# 16.net
KiCad netlist of a schematic drawn in Altium Designer
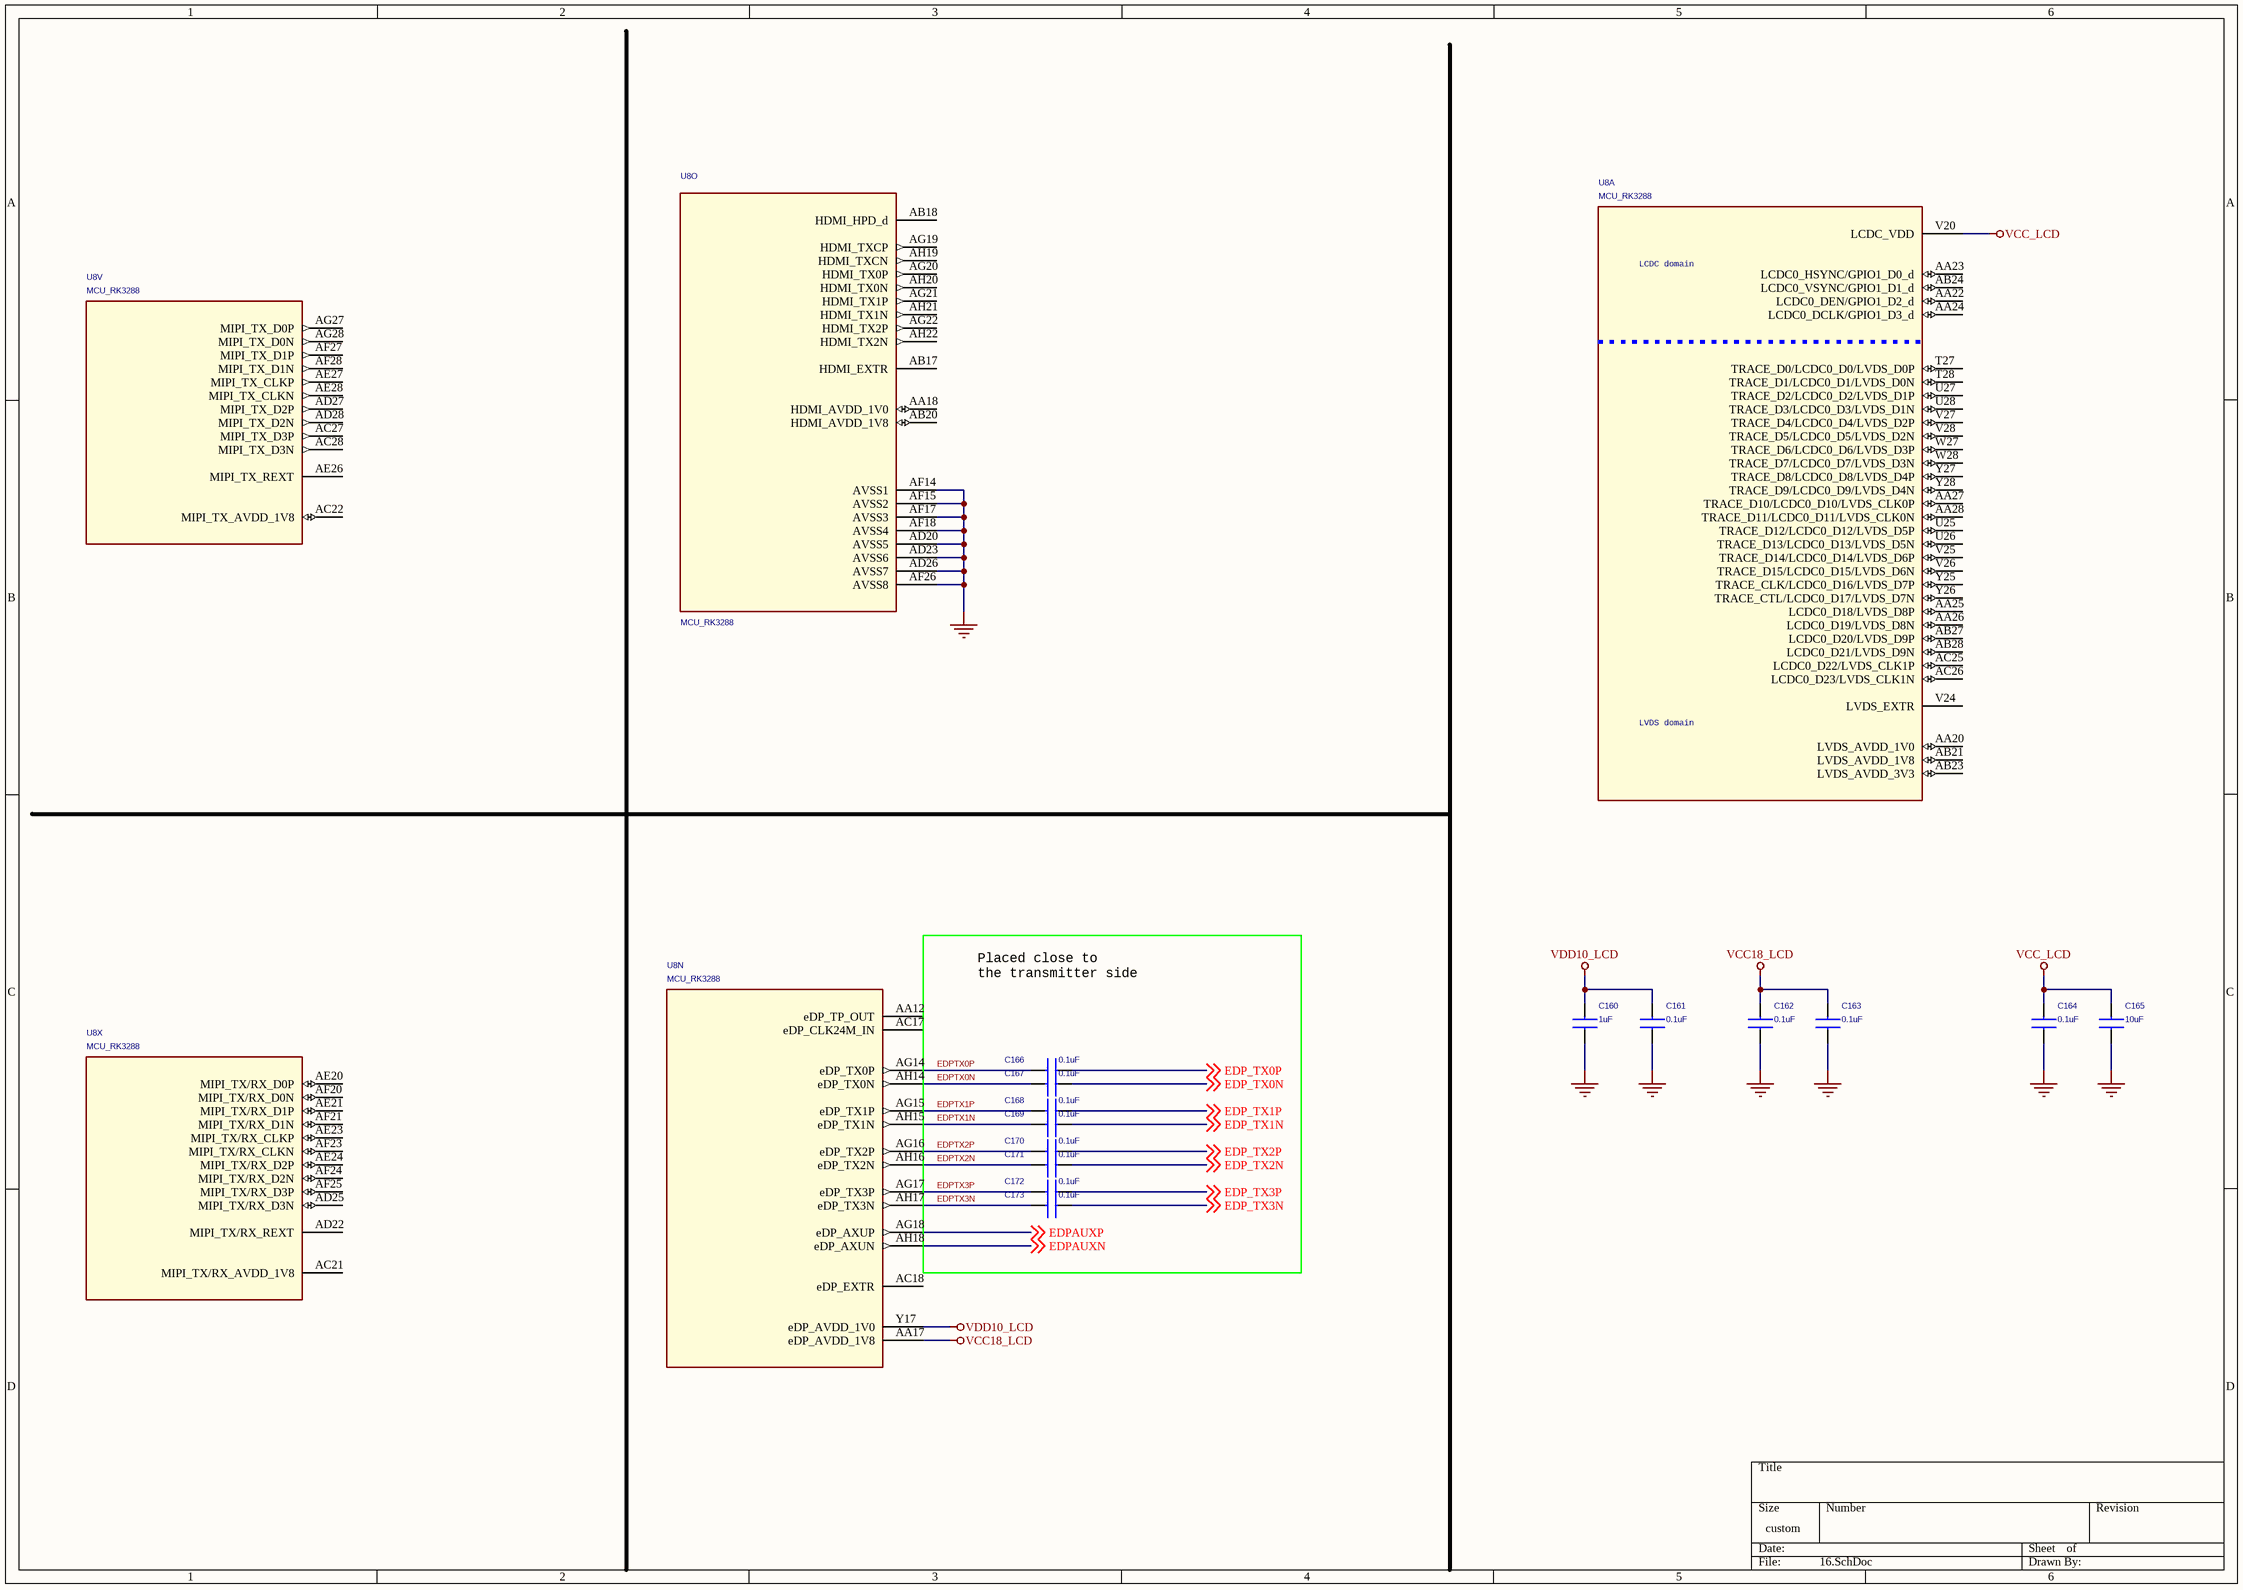
[diagram p0: 16.SchDoc]

(export (version "E")
  (design (tool "Eeschema 10.0.6"))
  (components
    (comp (ref "C160")
      (value "1uF")
      (footprint "C0603")
      (description "CAP,MLCC,100nF,+/-10%,X7R,6.3V,SMD0402")
      (libsource (lib "*") (part "CAP NP_Dup3"))
    )
    (comp (ref "C161")
      (value "0.1uF")
      (footprint "C0603")
      (description "CAP,MLCC,100nF,+/-10%,X7R,6.3V,SMD0402")
      (libsource (lib "*") (part "CAP NP_Dup3"))
    )
    (comp (ref "C162")
      (value "0.1uF")
      (footprint "C0603")
      (description "CAP,MLCC,100nF,+/-10%,X7R,6.3V,SMD0402")
      (libsource (lib "*") (part "CAP NP_Dup3"))
    )
    (comp (ref "C163")
      (value "0.1uF")
      (footprint "C0603")
      (description "CAP,MLCC,100nF,+/-10%,X7R,6.3V,SMD0402")
      (libsource (lib "*") (part "CAP NP_Dup3"))
    )
    (comp (ref "C164")
      (value "0.1uF")
      (footprint "C0603")
      (description "CAP,MLCC,100nF,+/-10%,X7R,6.3V,SMD0402")
      (libsource (lib "*") (part "CAP NP_Dup3"))
    )
    (comp (ref "C165")
      (value "10uF")
      (footprint "C0603")
      (description "CAP,MLCC,4.7uF,+/-10%,X5R,6.3V,SMD0603")
      (libsource (lib "*") (part "CAP NP_Dup3"))
    )
    (comp (ref "C166")
      (value "0.1uF")
      (footprint "C0603")
      (description "CAP,MLCC,100nF,+/-10%,X7R,6.3V,SMD0402")
      (libsource (lib "*") (part "CAP NP_Dup3"))
    )
    (comp (ref "C167")
      (value "0.1uF")
      (footprint "C0603")
      (description "CAP,MLCC,100nF,+/-10%,X7R,6.3V,SMD0402")
      (libsource (lib "*") (part "CAP NP_Dup3"))
    )
    (comp (ref "C168")
      (value "0.1uF")
      (footprint "C0603")
      (description "CAP,MLCC,100nF,+/-10%,X7R,6.3V,SMD0402")
      (libsource (lib "*") (part "CAP NP_Dup3"))
    )
    (comp (ref "C169")
      (value "0.1uF")
      (footprint "C0603")
      (description "CAP,MLCC,100nF,+/-10%,X7R,6.3V,SMD0402")
      (libsource (lib "*") (part "CAP NP_Dup3"))
    )
    (comp (ref "C170")
      (value "0.1uF")
      (footprint "C0603")
      (description "CAP,MLCC,100nF,+/-10%,X7R,6.3V,SMD0402")
      (libsource (lib "*") (part "CAP NP_Dup3"))
    )
    (comp (ref "C171")
      (value "0.1uF")
      (footprint "C0603")
      (description "CAP,MLCC,100nF,+/-10%,X7R,6.3V,SMD0402")
      (libsource (lib "*") (part "CAP NP_Dup3"))
    )
    (comp (ref "C172")
      (value "0.1uF")
      (footprint "C0603")
      (description "CAP,MLCC,100nF,+/-10%,X7R,6.3V,SMD0402")
      (libsource (lib "*") (part "CAP NP_Dup3"))
    )
    (comp (ref "C173")
      (value "0.1uF")
      (footprint "C0603")
      (description "CAP,MLCC,100nF,+/-10%,X7R,6.3V,SMD0402")
      (libsource (lib "*") (part "CAP NP_Dup3"))
    )
    (comp (ref "U8")
      (value "MCU_RK3288")
      (footprint "BGA453-19X19")
      (libsource (lib "*") (part "MCU_RK3288_3"))
    )
  )
  (nets
    (net (code "1") (name "/EDPTX0N") (class "Default")
      (node (ref "C167") (pin "1") (pinfunction "1_1") (pintype "passive"))
      (node (ref "U8") (pin "AH14") (pinfunction "eDP_TX0N_AH14") (pintype "output"))
    )
    (net (code "2") (name "/EDPTX0P") (class "Default")
      (node (ref "C166") (pin "1") (pinfunction "1_1") (pintype "passive"))
      (node (ref "U8") (pin "AG14") (pinfunction "eDP_TX0P_AG14") (pintype "output"))
    )
    (net (code "3") (name "/EDPTX1N") (class "Default")
      (node (ref "C169") (pin "1") (pinfunction "1_1") (pintype "passive"))
      (node (ref "U8") (pin "AH15") (pinfunction "eDP_TX1N_AH15") (pintype "output"))
    )
    (net (code "4") (name "/EDPTX1P") (class "Default")
      (node (ref "C168") (pin "1") (pinfunction "1_1") (pintype "passive"))
      (node (ref "U8") (pin "AG15") (pinfunction "eDP_TX1P_AG15") (pintype "output"))
    )
    (net (code "5") (name "/EDPTX2N") (class "Default")
      (node (ref "C171") (pin "1") (pinfunction "1_1") (pintype "passive"))
      (node (ref "U8") (pin "AH16") (pinfunction "eDP_TX2N_AH16") (pintype "output"))
    )
    (net (code "6") (name "/EDPTX2P") (class "Default")
      (node (ref "C170") (pin "1") (pinfunction "1_1") (pintype "passive"))
      (node (ref "U8") (pin "AG16") (pinfunction "eDP_TX2P_AG16") (pintype "output"))
    )
    (net (code "7") (name "/EDPTX3N") (class "Default")
      (node (ref "C173") (pin "1") (pinfunction "1_1") (pintype "passive"))
      (node (ref "U8") (pin "AH17") (pinfunction "eDP_TX3N_AH17") (pintype "output"))
    )
    (net (code "8") (name "/EDPTX3P") (class "Default")
      (node (ref "C172") (pin "1") (pinfunction "1_1") (pintype "passive"))
      (node (ref "U8") (pin "AG17") (pinfunction "eDP_TX3P_AG17") (pintype "output"))
    )
    (net (code "9") (name "EDPAUXN") (class "Default")
      (node (ref "U8") (pin "AH18") (pinfunction "eDP_AXUN_AH18") (pintype "output"))
    )
    (net (code "10") (name "EDPAUXP") (class "Default")
      (node (ref "U8") (pin "AG18") (pinfunction "eDP_AXUP_AG18") (pintype "output"))
    )
    (net (code "11") (name "EDP_TX0N") (class "Default")
      (node (ref "C167") (pin "2") (pinfunction "2_2") (pintype "passive"))
    )
    (net (code "12") (name "EDP_TX0P") (class "Default")
      (node (ref "C166") (pin "2") (pinfunction "2_2") (pintype "passive"))
    )
    (net (code "13") (name "EDP_TX1N") (class "Default")
      (node (ref "C169") (pin "2") (pinfunction "2_2") (pintype "passive"))
    )
    (net (code "14") (name "EDP_TX1P") (class "Default")
      (node (ref "C168") (pin "2") (pinfunction "2_2") (pintype "passive"))
    )
    (net (code "15") (name "EDP_TX2N") (class "Default")
      (node (ref "C171") (pin "2") (pinfunction "2_2") (pintype "passive"))
    )
    (net (code "16") (name "EDP_TX2P") (class "Default")
      (node (ref "C170") (pin "2") (pinfunction "2_2") (pintype "passive"))
    )
    (net (code "17") (name "EDP_TX3N") (class "Default")
      (node (ref "C173") (pin "2") (pinfunction "2_2") (pintype "passive"))
    )
    (net (code "18") (name "EDP_TX3P") (class "Default")
      (node (ref "C172") (pin "2") (pinfunction "2_2") (pintype "passive"))
    )
    (net (code "19") (name "GND") (class "Default")
      (node (ref "C160") (pin "2") (pinfunction "2_2") (pintype "passive"))
      (node (ref "C161") (pin "2") (pinfunction "2_2") (pintype "passive"))
      (node (ref "C162") (pin "2") (pinfunction "2_2") (pintype "passive"))
      (node (ref "C163") (pin "2") (pinfunction "2_2") (pintype "passive"))
      (node (ref "C164") (pin "2") (pinfunction "2_2") (pintype "passive"))
      (node (ref "C165") (pin "2") (pinfunction "2_2") (pintype "passive"))
      (node (ref "U8") (pin "AD20") (pinfunction "AVSS5_AD20") (pintype "power_in"))
      (node (ref "U8") (pin "AD23") (pinfunction "AVSS6_AD23") (pintype "power_in"))
      (node (ref "U8") (pin "AD26") (pinfunction "AVSS7_AD26") (pintype "power_in"))
      (node (ref "U8") (pin "AF14") (pinfunction "AVSS1_AF14") (pintype "power_in"))
      (node (ref "U8") (pin "AF15") (pinfunction "AVSS2_AF15") (pintype "power_in"))
      (node (ref "U8") (pin "AF17") (pinfunction "AVSS3_AF17") (pintype "power_in"))
      (node (ref "U8") (pin "AF18") (pinfunction "AVSS4_AF18") (pintype "power_in"))
      (node (ref "U8") (pin "AF26") (pinfunction "AVSS8_AF26") (pintype "power_in"))
    )
    (net (code "20") (name "VCC18_LCD") (class "Default")
      (node (ref "C162") (pin "1") (pinfunction "1_1") (pintype "passive"))
      (node (ref "C163") (pin "1") (pinfunction "1_1") (pintype "passive"))
      (node (ref "U8") (pin "AA17") (pinfunction "eDP_AVDD_1V8_AA17") (pintype "power_in"))
    )
    (net (code "21") (name "VCC_LCD") (class "Default")
      (node (ref "C164") (pin "1") (pinfunction "1_1") (pintype "passive"))
      (node (ref "C165") (pin "1") (pinfunction "1_1") (pintype "passive"))
      (node (ref "U8") (pin "V20") (pinfunction "LCDC_VDD_V20") (pintype "power_in"))
    )
    (net (code "22") (name "VDD10_LCD") (class "Default")
      (node (ref "C160") (pin "1") (pinfunction "1_1") (pintype "passive"))
      (node (ref "C161") (pin "1") (pinfunction "1_1") (pintype "passive"))
      (node (ref "U8") (pin "Y17") (pinfunction "eDP_AVDD_1V0_Y17") (pintype "power_in"))
    )
    (net (code "23") (name "unconnected-(U8A-LCDC0_D18{slash}LVDS_D8P-PadAA25)") (class "Default")
      (node (ref "U8") (pin "AA25") (pinfunction "LCDC0_D18/LVDS_D8P_AA25") (pintype "bidirectional"))
    )
    (net (code "24") (name "unconnected-(U8A-LCDC0_D19{slash}LVDS_D8N-PadAA26)") (class "Default")
      (node (ref "U8") (pin "AA26") (pinfunction "LCDC0_D19/LVDS_D8N_AA26") (pintype "bidirectional"))
    )
    (net (code "25") (name "unconnected-(U8A-LCDC0_D20{slash}LVDS_D9P-PadAB27)") (class "Default")
      (node (ref "U8") (pin "AB27") (pinfunction "LCDC0_D20/LVDS_D9P_AB27") (pintype "bidirectional"))
    )
    (net (code "26") (name "unconnected-(U8A-LCDC0_D21{slash}LVDS_D9N-PadAB28)") (class "Default")
      (node (ref "U8") (pin "AB28") (pinfunction "LCDC0_D21/LVDS_D9N_AB28") (pintype "bidirectional"))
    )
    (net (code "27") (name "unconnected-(U8A-LCDC0_D22{slash}LVDS_CLK1P-PadAC25)") (class "Default")
      (node (ref "U8") (pin "AC25") (pinfunction "LCDC0_D22/LVDS_CLK1P_AC25") (pintype "bidirectional"))
    )
    (net (code "28") (name "unconnected-(U8A-LCDC0_D23{slash}LVDS_CLK1N-PadAC26)") (class "Default")
      (node (ref "U8") (pin "AC26") (pinfunction "LCDC0_D23/LVDS_CLK1N_AC26") (pintype "bidirectional"))
    )
    (net (code "29") (name "unconnected-(U8A-LCDC0_DCLK{slash}GPIO1_D3_d-PadAA24)") (class "Default")
      (node (ref "U8") (pin "AA24") (pinfunction "LCDC0_DCLK/GPIO1_D3_d_AA24") (pintype "bidirectional"))
    )
    (net (code "30") (name "unconnected-(U8A-LCDC0_DEN{slash}GPIO1_D2_d-PadAA22)") (class "Default")
      (node (ref "U8") (pin "AA22") (pinfunction "LCDC0_DEN/GPIO1_D2_d_AA22") (pintype "bidirectional"))
    )
    (net (code "31") (name "unconnected-(U8A-LCDC0_HSYNC{slash}GPIO1_D0_d-PadAA23)") (class "Default")
      (node (ref "U8") (pin "AA23") (pinfunction "LCDC0_HSYNC/GPIO1_D0_d_AA23") (pintype "bidirectional"))
    )
    (net (code "32") (name "unconnected-(U8A-LCDC0_VSYNC{slash}GPIO1_D1_d-PadAB24)") (class "Default")
      (node (ref "U8") (pin "AB24") (pinfunction "LCDC0_VSYNC/GPIO1_D1_d_AB24") (pintype "bidirectional"))
    )
    (net (code "33") (name "unconnected-(U8A-LVDS_AVDD_1V0-PadAA20)") (class "Default")
      (node (ref "U8") (pin "AA20") (pinfunction "LVDS_AVDD_1V0_AA20") (pintype "bidirectional"))
    )
    (net (code "34") (name "unconnected-(U8A-LVDS_AVDD_1V8-PadAB21)") (class "Default")
      (node (ref "U8") (pin "AB21") (pinfunction "LVDS_AVDD_1V8_AB21") (pintype "bidirectional"))
    )
    (net (code "35") (name "unconnected-(U8A-LVDS_AVDD_3V3-PadAB23)") (class "Default")
      (node (ref "U8") (pin "AB23") (pinfunction "LVDS_AVDD_3V3_AB23") (pintype "bidirectional"))
    )
    (net (code "36") (name "unconnected-(U8A-LVDS_EXTR-PadV24)") (class "Default")
      (node (ref "U8") (pin "V24") (pinfunction "LVDS_EXTR_V24") (pintype "passive"))
    )
    (net (code "37") (name "unconnected-(U8A-TRACE_CLK{slash}LCDC0_D16{slash}LVDS_D7P-PadY25)") (class "Default")
      (node (ref "U8") (pin "Y25") (pinfunction "TRACE_CLK/LCDC0_D16/LVDS_D7P_Y25") (pintype "bidirectional"))
    )
    (net (code "38") (name "unconnected-(U8A-TRACE_CTL{slash}LCDC0_D17{slash}LVDS_D7N-PadY26)") (class "Default")
      (node (ref "U8") (pin "Y26") (pinfunction "TRACE_CTL/LCDC0_D17/LVDS_D7N_Y26") (pintype "bidirectional"))
    )
    (net (code "39") (name "unconnected-(U8A-TRACE_D0{slash}LCDC0_D0{slash}LVDS_D0P-PadT27)") (class "Default")
      (node (ref "U8") (pin "T27") (pinfunction "TRACE_D0/LCDC0_D0/LVDS_D0P_T27") (pintype "bidirectional"))
    )
    (net (code "40") (name "unconnected-(U8A-TRACE_D1{slash}LCDC0_D1{slash}LVDS_D0N-PadT28)") (class "Default")
      (node (ref "U8") (pin "T28") (pinfunction "TRACE_D1/LCDC0_D1/LVDS_D0N_T28") (pintype "bidirectional"))
    )
    (net (code "41") (name "unconnected-(U8A-TRACE_D2{slash}LCDC0_D2{slash}LVDS_D1P-PadU27)") (class "Default")
      (node (ref "U8") (pin "U27") (pinfunction "TRACE_D2/LCDC0_D2/LVDS_D1P_U27") (pintype "bidirectional"))
    )
    (net (code "42") (name "unconnected-(U8A-TRACE_D3{slash}LCDC0_D3{slash}LVDS_D1N-PadU28)") (class "Default")
      (node (ref "U8") (pin "U28") (pinfunction "TRACE_D3/LCDC0_D3/LVDS_D1N_U28") (pintype "bidirectional"))
    )
    (net (code "43") (name "unconnected-(U8A-TRACE_D4{slash}LCDC0_D4{slash}LVDS_D2P-PadV27)") (class "Default")
      (node (ref "U8") (pin "V27") (pinfunction "TRACE_D4/LCDC0_D4/LVDS_D2P_V27") (pintype "bidirectional"))
    )
    (net (code "44") (name "unconnected-(U8A-TRACE_D5{slash}LCDC0_D5{slash}LVDS_D2N-PadV28)") (class "Default")
      (node (ref "U8") (pin "V28") (pinfunction "TRACE_D5/LCDC0_D5/LVDS_D2N_V28") (pintype "bidirectional"))
    )
    (net (code "45") (name "unconnected-(U8A-TRACE_D6{slash}LCDC0_D6{slash}LVDS_D3P-PadW27)") (class "Default")
      (node (ref "U8") (pin "W27") (pinfunction "TRACE_D6/LCDC0_D6/LVDS_D3P_W27") (pintype "bidirectional"))
    )
    (net (code "46") (name "unconnected-(U8A-TRACE_D7{slash}LCDC0_D7{slash}LVDS_D3N-PadW28)") (class "Default")
      (node (ref "U8") (pin "W28") (pinfunction "TRACE_D7/LCDC0_D7/LVDS_D3N_W28") (pintype "bidirectional"))
    )
    (net (code "47") (name "unconnected-(U8A-TRACE_D8{slash}LCDC0_D8{slash}LVDS_D4P-PadY27)") (class "Default")
      (node (ref "U8") (pin "Y27") (pinfunction "TRACE_D8/LCDC0_D8/LVDS_D4P_Y27") (pintype "bidirectional"))
    )
    (net (code "48") (name "unconnected-(U8A-TRACE_D9{slash}LCDC0_D9{slash}LVDS_D4N-PadY28)") (class "Default")
      (node (ref "U8") (pin "Y28") (pinfunction "TRACE_D9/LCDC0_D9/LVDS_D4N_Y28") (pintype "bidirectional"))
    )
    (net (code "49") (name "unconnected-(U8A-TRACE_D10{slash}LCDC0_D10{slash}LVDS_CLK0P-PadAA27)") (class "Default")
      (node (ref "U8") (pin "AA27") (pinfunction "TRACE_D10/LCDC0_D10/LVDS_CLK0P_AA27") (pintype "bidirectional"))
    )
    (net (code "50") (name "unconnected-(U8A-TRACE_D11{slash}LCDC0_D11{slash}LVDS_CLK0N-PadAA28)") (class "Default")
      (node (ref "U8") (pin "AA28") (pinfunction "TRACE_D11/LCDC0_D11/LVDS_CLK0N_AA28") (pintype "bidirectional"))
    )
    (net (code "51") (name "unconnected-(U8A-TRACE_D12{slash}LCDC0_D12{slash}LVDS_D5P-PadU25)") (class "Default")
      (node (ref "U8") (pin "U25") (pinfunction "TRACE_D12/LCDC0_D12/LVDS_D5P_U25") (pintype "bidirectional"))
    )
    (net (code "52") (name "unconnected-(U8A-TRACE_D13{slash}LCDC0_D13{slash}LVDS_D5N-PadU26)") (class "Default")
      (node (ref "U8") (pin "U26") (pinfunction "TRACE_D13/LCDC0_D13/LVDS_D5N_U26") (pintype "bidirectional"))
    )
    (net (code "53") (name "unconnected-(U8A-TRACE_D14{slash}LCDC0_D14{slash}LVDS_D6P-PadV25)") (class "Default")
      (node (ref "U8") (pin "V25") (pinfunction "TRACE_D14/LCDC0_D14/LVDS_D6P_V25") (pintype "bidirectional"))
    )
    (net (code "54") (name "unconnected-(U8A-TRACE_D15{slash}LCDC0_D15{slash}LVDS_D6N-PadV26)") (class "Default")
      (node (ref "U8") (pin "V26") (pinfunction "TRACE_D15/LCDC0_D15/LVDS_D6N_V26") (pintype "bidirectional"))
    )
    (net (code "55") (name "unconnected-(U8N-eDP_CLK24M_IN-PadAC17)") (class "Default")
      (node (ref "U8") (pin "AC17") (pinfunction "eDP_CLK24M_IN_AC17") (pintype "passive"))
    )
    (net (code "56") (name "unconnected-(U8N-eDP_EXTR-PadAC18)") (class "Default")
      (node (ref "U8") (pin "AC18") (pinfunction "eDP_EXTR_AC18") (pintype "passive"))
    )
    (net (code "57") (name "unconnected-(U8N-eDP_TP_OUT-PadAA12)") (class "Default")
      (node (ref "U8") (pin "AA12") (pinfunction "eDP_TP_OUT_AA12") (pintype "passive"))
    )
    (net (code "58") (name "unconnected-(U8O-HDMI_AVDD_1V0-PadAA18)") (class "Default")
      (node (ref "U8") (pin "AA18") (pinfunction "HDMI_AVDD_1V0_AA18") (pintype "bidirectional"))
    )
    (net (code "59") (name "unconnected-(U8O-HDMI_AVDD_1V8-PadAB20)") (class "Default")
      (node (ref "U8") (pin "AB20") (pinfunction "HDMI_AVDD_1V8_AB20") (pintype "bidirectional"))
    )
    (net (code "60") (name "unconnected-(U8O-HDMI_EXTR-PadAB17)") (class "Default")
      (node (ref "U8") (pin "AB17") (pinfunction "HDMI_EXTR_AB17") (pintype "passive"))
    )
    (net (code "61") (name "unconnected-(U8O-HDMI_HPD_d-PadAB18)") (class "Default")
      (node (ref "U8") (pin "AB18") (pinfunction "HDMI_HPD_d_AB18") (pintype "passive"))
    )
    (net (code "62") (name "unconnected-(U8O-HDMI_TX0N-PadAH20)") (class "Default")
      (node (ref "U8") (pin "AH20") (pinfunction "HDMI_TX0N_AH20") (pintype "output"))
    )
    (net (code "63") (name "unconnected-(U8O-HDMI_TX0P-PadAG20)") (class "Default")
      (node (ref "U8") (pin "AG20") (pinfunction "HDMI_TX0P_AG20") (pintype "output"))
    )
    (net (code "64") (name "unconnected-(U8O-HDMI_TX1N-PadAH21)") (class "Default")
      (node (ref "U8") (pin "AH21") (pinfunction "HDMI_TX1N_AH21") (pintype "output"))
    )
    (net (code "65") (name "unconnected-(U8O-HDMI_TX1P-PadAG21)") (class "Default")
      (node (ref "U8") (pin "AG21") (pinfunction "HDMI_TX1P_AG21") (pintype "output"))
    )
    (net (code "66") (name "unconnected-(U8O-HDMI_TX2N-PadAH22)") (class "Default")
      (node (ref "U8") (pin "AH22") (pinfunction "HDMI_TX2N_AH22") (pintype "output"))
    )
    (net (code "67") (name "unconnected-(U8O-HDMI_TX2P-PadAG22)") (class "Default")
      (node (ref "U8") (pin "AG22") (pinfunction "HDMI_TX2P_AG22") (pintype "output"))
    )
    (net (code "68") (name "unconnected-(U8O-HDMI_TXCN-PadAH19)") (class "Default")
      (node (ref "U8") (pin "AH19") (pinfunction "HDMI_TXCN_AH19") (pintype "output"))
    )
    (net (code "69") (name "unconnected-(U8O-HDMI_TXCP-PadAG19)") (class "Default")
      (node (ref "U8") (pin "AG19") (pinfunction "HDMI_TXCP_AG19") (pintype "output"))
    )
    (net (code "70") (name "unconnected-(U8V-MIPI_TX_AVDD_1V8-PadAC22)") (class "Default")
      (node (ref "U8") (pin "AC22") (pinfunction "MIPI_TX_AVDD_1V8_AC22") (pintype "bidirectional"))
    )
    (net (code "71") (name "unconnected-(U8V-MIPI_TX_CLKN-PadAE28)") (class "Default")
      (node (ref "U8") (pin "AE28") (pinfunction "MIPI_TX_CLKN_AE28") (pintype "output"))
    )
    (net (code "72") (name "unconnected-(U8V-MIPI_TX_CLKP-PadAE27)") (class "Default")
      (node (ref "U8") (pin "AE27") (pinfunction "MIPI_TX_CLKP_AE27") (pintype "output"))
    )
    (net (code "73") (name "unconnected-(U8V-MIPI_TX_D0N-PadAG28)") (class "Default")
      (node (ref "U8") (pin "AG28") (pinfunction "MIPI_TX_D0N_AG28") (pintype "output"))
    )
    (net (code "74") (name "unconnected-(U8V-MIPI_TX_D0P-PadAG27)") (class "Default")
      (node (ref "U8") (pin "AG27") (pinfunction "MIPI_TX_D0P_AG27") (pintype "output"))
    )
    (net (code "75") (name "unconnected-(U8V-MIPI_TX_D1N-PadAF28)") (class "Default")
      (node (ref "U8") (pin "AF28") (pinfunction "MIPI_TX_D1N_AF28") (pintype "output"))
    )
    (net (code "76") (name "unconnected-(U8V-MIPI_TX_D1P-PadAF27)") (class "Default")
      (node (ref "U8") (pin "AF27") (pinfunction "MIPI_TX_D1P_AF27") (pintype "output"))
    )
    (net (code "77") (name "unconnected-(U8V-MIPI_TX_D2N-PadAD28)") (class "Default")
      (node (ref "U8") (pin "AD28") (pinfunction "MIPI_TX_D2N_AD28") (pintype "output"))
    )
    (net (code "78") (name "unconnected-(U8V-MIPI_TX_D2P-PadAD27)") (class "Default")
      (node (ref "U8") (pin "AD27") (pinfunction "MIPI_TX_D2P_AD27") (pintype "output"))
    )
    (net (code "79") (name "unconnected-(U8V-MIPI_TX_D3N-PadAC28)") (class "Default")
      (node (ref "U8") (pin "AC28") (pinfunction "MIPI_TX_D3N_AC28") (pintype "output"))
    )
    (net (code "80") (name "unconnected-(U8V-MIPI_TX_D3P-PadAC27)") (class "Default")
      (node (ref "U8") (pin "AC27") (pinfunction "MIPI_TX_D3P_AC27") (pintype "output"))
    )
    (net (code "81") (name "unconnected-(U8V-MIPI_TX_REXT-PadAE26)") (class "Default")
      (node (ref "U8") (pin "AE26") (pinfunction "MIPI_TX_REXT_AE26") (pintype "passive"))
    )
    (net (code "82") (name "unconnected-(U8X-MIPI_TX{slash}RX_AVDD_1V8-PadAC21)") (class "Default")
      (node (ref "U8") (pin "AC21") (pinfunction "MIPI_TX/RX_AVDD_1V8_AC21") (pintype "power_in"))
    )
    (net (code "83") (name "unconnected-(U8X-MIPI_TX{slash}RX_CLKN-PadAF23)") (class "Default")
      (node (ref "U8") (pin "AF23") (pinfunction "MIPI_TX/RX_CLKN_AF23") (pintype "bidirectional"))
    )
    (net (code "84") (name "unconnected-(U8X-MIPI_TX{slash}RX_CLKP-PadAE23)") (class "Default")
      (node (ref "U8") (pin "AE23") (pinfunction "MIPI_TX/RX_CLKP_AE23") (pintype "bidirectional"))
    )
    (net (code "85") (name "unconnected-(U8X-MIPI_TX{slash}RX_D0N-PadAF20)") (class "Default")
      (node (ref "U8") (pin "AF20") (pinfunction "MIPI_TX/RX_D0N_AF20") (pintype "bidirectional"))
    )
    (net (code "86") (name "unconnected-(U8X-MIPI_TX{slash}RX_D0P-PadAE20)") (class "Default")
      (node (ref "U8") (pin "AE20") (pinfunction "MIPI_TX/RX_D0P_AE20") (pintype "bidirectional"))
    )
    (net (code "87") (name "unconnected-(U8X-MIPI_TX{slash}RX_D1N-PadAF21)") (class "Default")
      (node (ref "U8") (pin "AF21") (pinfunction "MIPI_TX/RX_D1N_AF21") (pintype "bidirectional"))
    )
    (net (code "88") (name "unconnected-(U8X-MIPI_TX{slash}RX_D1P-PadAE21)") (class "Default")
      (node (ref "U8") (pin "AE21") (pinfunction "MIPI_TX/RX_D1P_AE21") (pintype "bidirectional"))
    )
    (net (code "89") (name "unconnected-(U8X-MIPI_TX{slash}RX_D2N-PadAF24)") (class "Default")
      (node (ref "U8") (pin "AF24") (pinfunction "MIPI_TX/RX_D2N_AF24") (pintype "bidirectional"))
    )
    (net (code "90") (name "unconnected-(U8X-MIPI_TX{slash}RX_D2P-PadAE24)") (class "Default")
      (node (ref "U8") (pin "AE24") (pinfunction "MIPI_TX/RX_D2P_AE24") (pintype "bidirectional"))
    )
    (net (code "91") (name "unconnected-(U8X-MIPI_TX{slash}RX_D3N-PadAD25)") (class "Default")
      (node (ref "U8") (pin "AD25") (pinfunction "MIPI_TX/RX_D3N_AD25") (pintype "bidirectional"))
    )
    (net (code "92") (name "unconnected-(U8X-MIPI_TX{slash}RX_D3P-PadAF25)") (class "Default")
      (node (ref "U8") (pin "AF25") (pinfunction "MIPI_TX/RX_D3P_AF25") (pintype "bidirectional"))
    )
    (net (code "93") (name "unconnected-(U8X-MIPI_TX{slash}RX_REXT-PadAD22)") (class "Default")
      (node (ref "U8") (pin "AD22") (pinfunction "MIPI_TX/RX_REXT_AD22") (pintype "passive"))
    )
  )
)
